# Automaton320.net
KiCad netlist of a schematic drawn in EAGLE
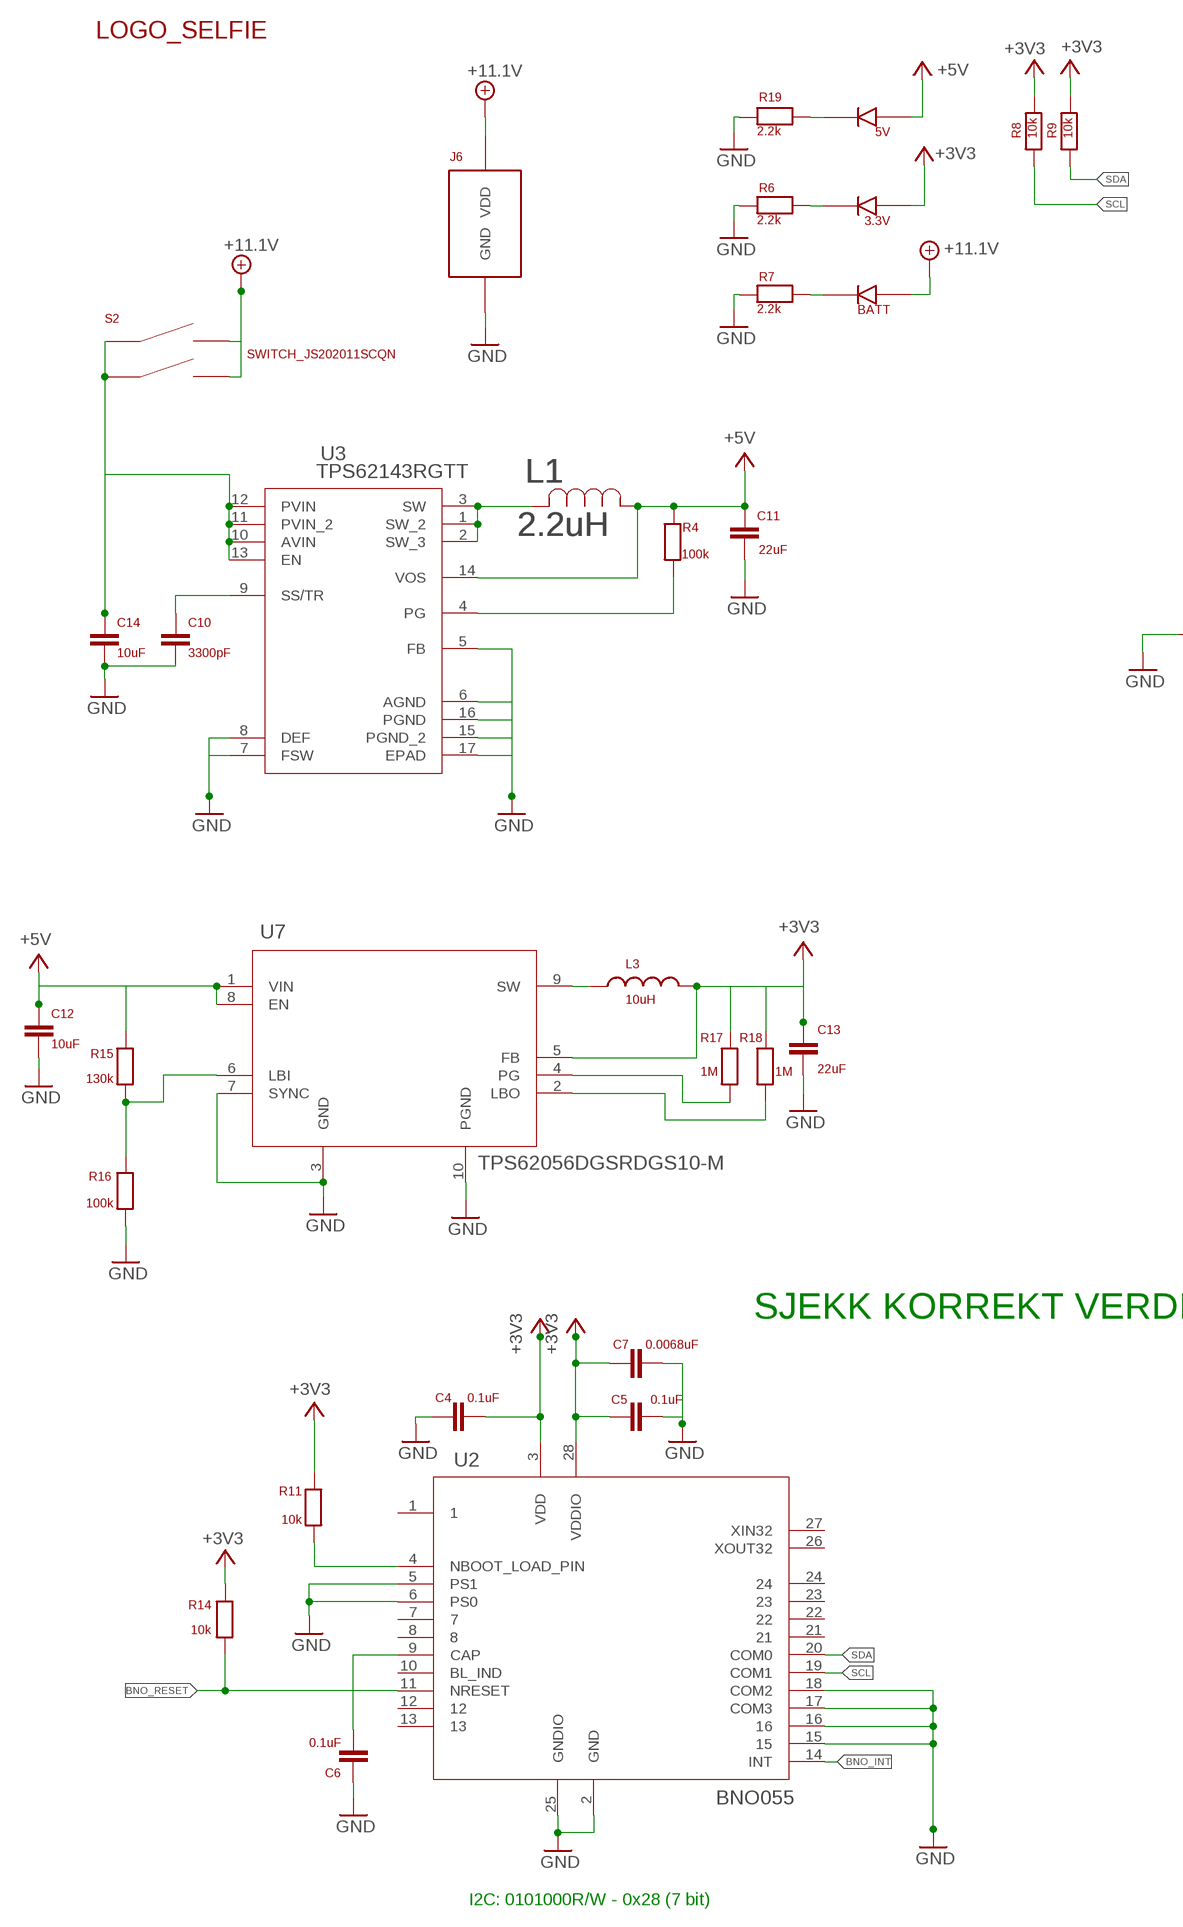
[diagram p0: schematic, sheet 1, part 1 of 2]
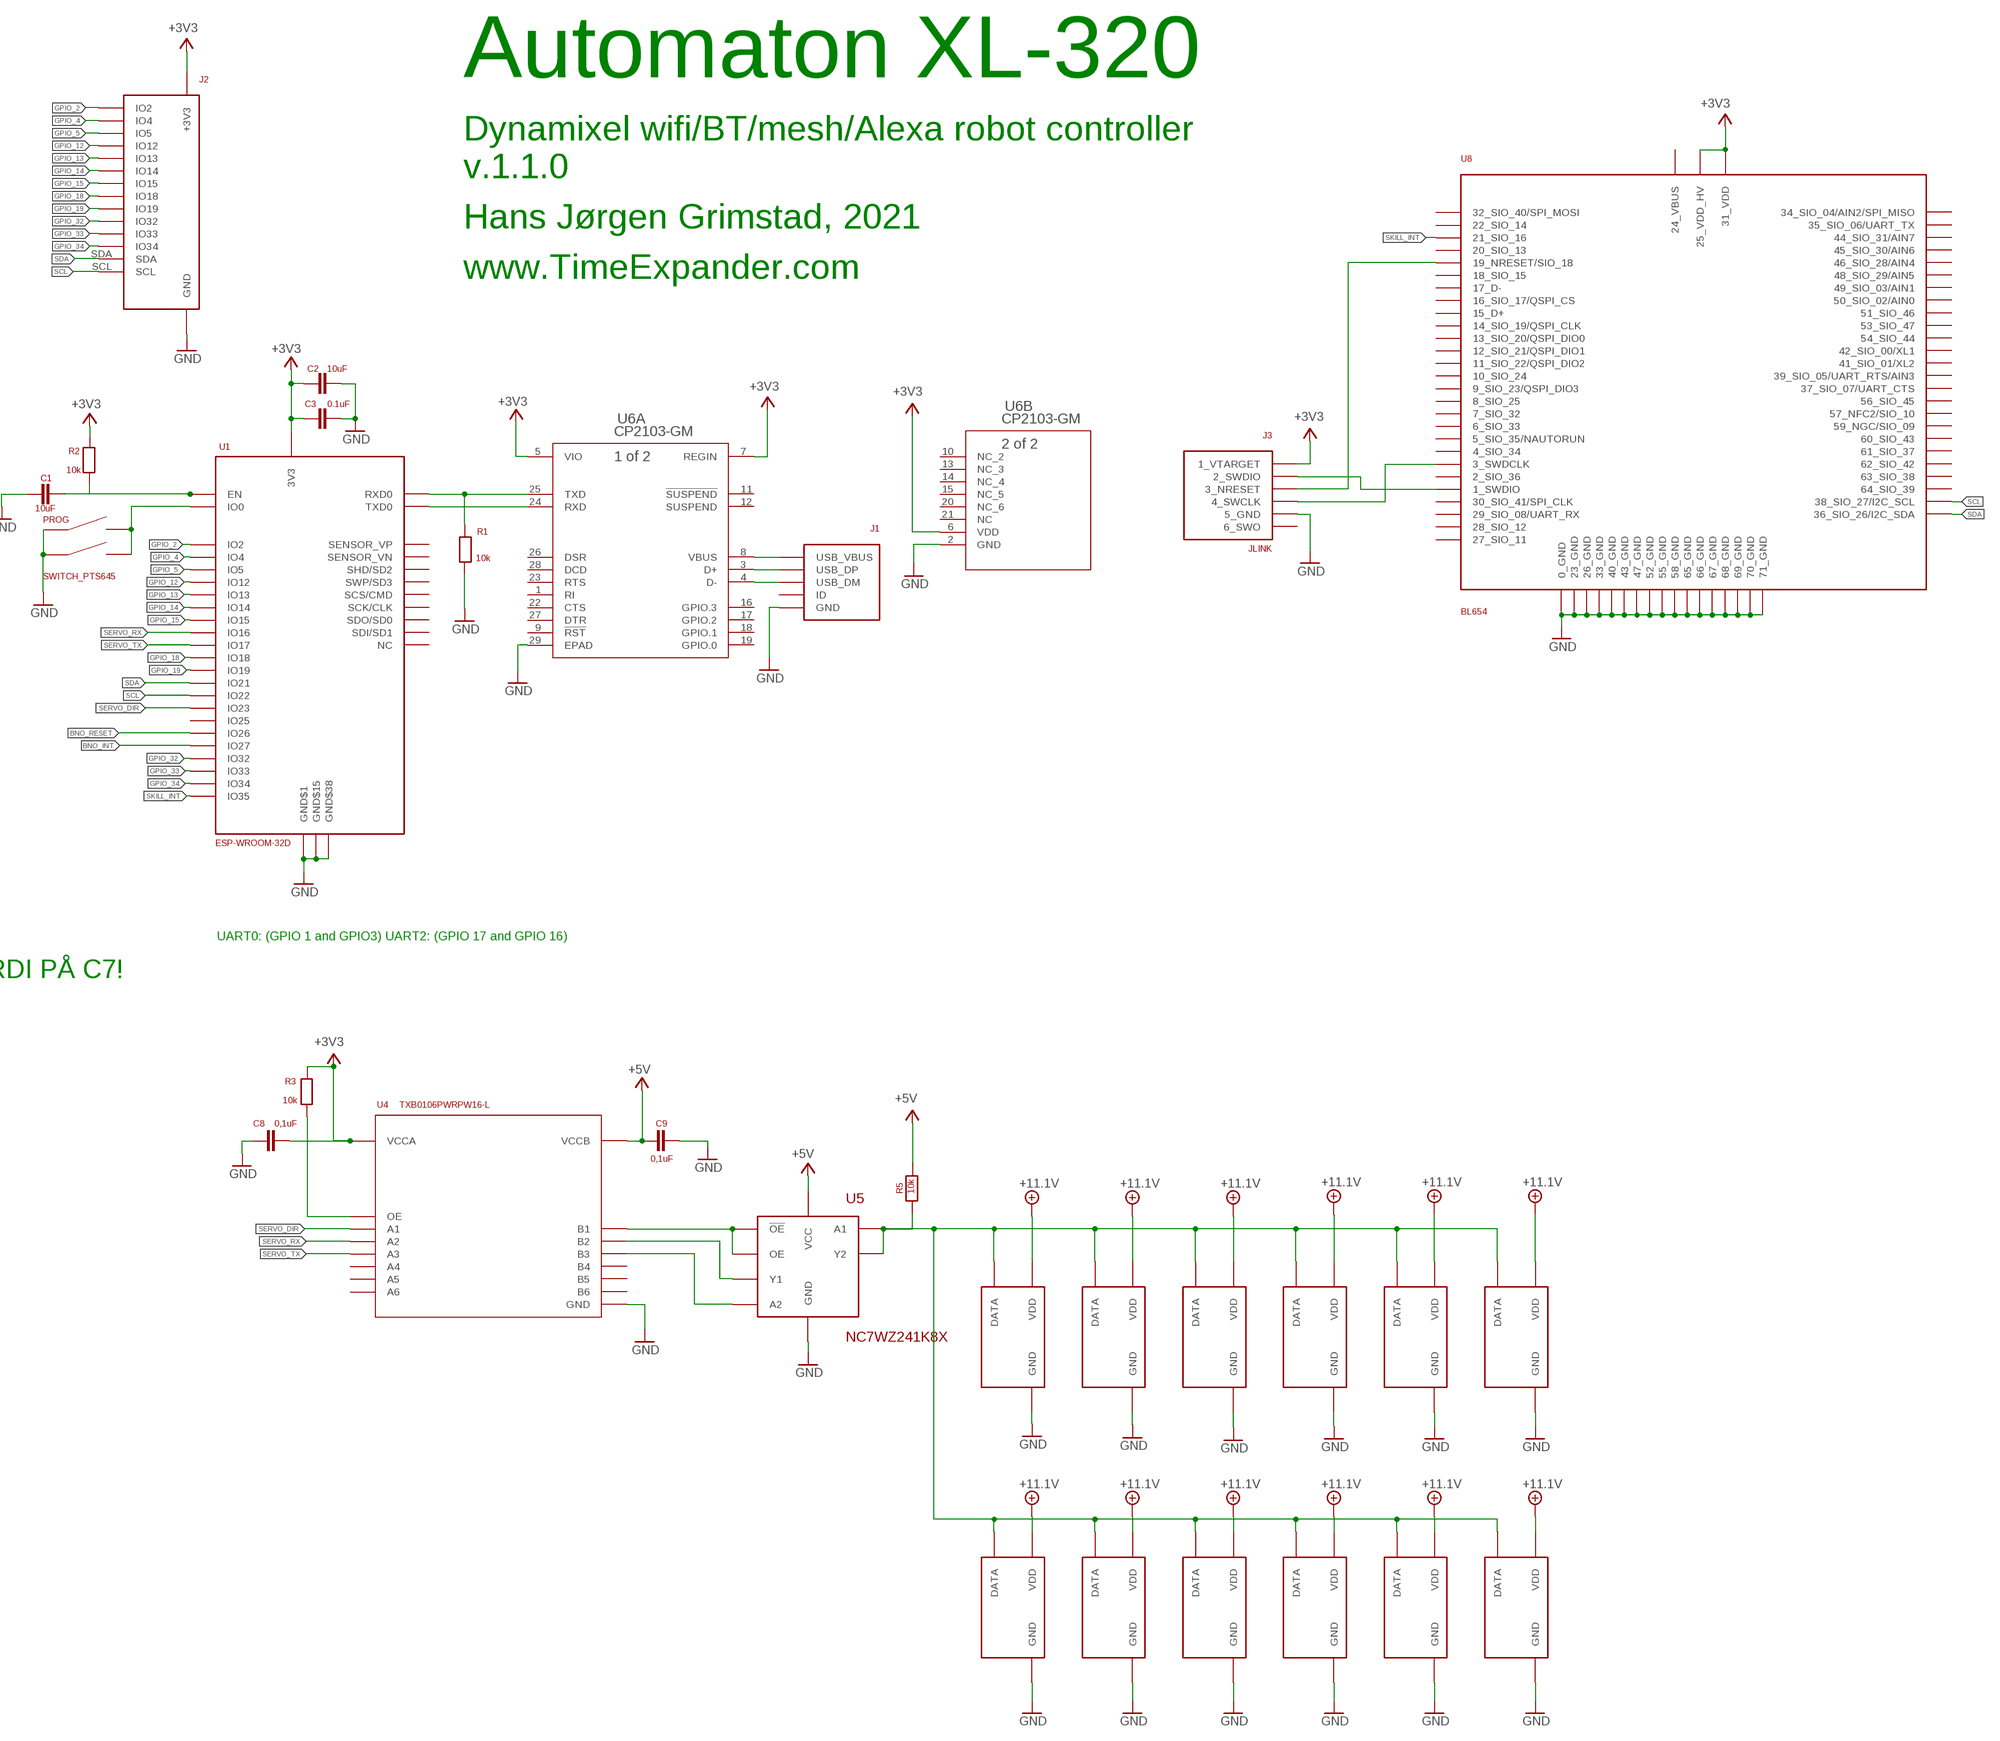
[diagram p1: schematic, sheet 1, part 2 of 2]

(export (version "E")
  (design (tool "Eeschema 10.0.6"))
  (components
    (comp (ref "3.3V")
      (value "LED_APTR3216PBC/A")
      (footprint "eagle-import:LED_APTR3216PBC_A")
      (libsource (lib "eagle-import") (part "LED_APTR3216PBC/A"))
    )
    (comp (ref "5V")
      (value "LED_APTR3216PBC/A")
      (footprint "eagle-import:LED_APTR3216PBC_A")
      (libsource (lib "eagle-import") (part "LED_APTR3216PBC/A"))
    )
    (comp (ref "BATT")
      (value "LED_APTR3216PBC/A")
      (footprint "eagle-import:LED_APTR3216PBC_A")
      (libsource (lib "eagle-import") (part "LED_APTR3216PBC/A"))
    )
    (comp (ref "C1")
      (value "10uF")
      (footprint "eagle-import:CAP_0402")
      (libsource (lib "eagle-import") (part "CAPACITOR0402"))
    )
    (comp (ref "C2")
      (value "10uF")
      (footprint "eagle-import:CAP_0402")
      (libsource (lib "eagle-import") (part "CAPACITOR0402"))
    )
    (comp (ref "C3")
      (value "0.1uF")
      (footprint "eagle-import:CAP_0402")
      (libsource (lib "eagle-import") (part "CAPACITOR0402"))
    )
    (comp (ref "C4")
      (value "0.1uF")
      (footprint "eagle-import:CAP_0402")
      (libsource (lib "eagle-import") (part "CAPACITOR0402"))
    )
    (comp (ref "C5")
      (value "0.1uF")
      (footprint "eagle-import:CAP_0402")
      (libsource (lib "eagle-import") (part "CAPACITOR0402"))
    )
    (comp (ref "C6")
      (value "0.1uF")
      (footprint "eagle-import:CAP_0402")
      (libsource (lib "eagle-import") (part "CAPACITOR0402"))
    )
    (comp (ref "C7")
      (value "0.0068uF")
      (footprint "eagle-import:CAP_0402")
      (libsource (lib "eagle-import") (part "CAPACITOR0402"))
    )
    (comp (ref "C8")
      (value "0,1uF")
      (footprint "eagle-import:CAP_0402")
      (libsource (lib "eagle-import") (part "CAPACITOR0402"))
    )
    (comp (ref "C9")
      (value "0,1uF")
      (footprint "eagle-import:CAP_0402")
      (libsource (lib "eagle-import") (part "CAPACITOR0402"))
    )
    (comp (ref "C10")
      (value "3300pF")
      (footprint "eagle-import:CAP_0402")
      (libsource (lib "eagle-import") (part "CAPACITOR0402"))
    )
    (comp (ref "C11")
      (value "22uF")
      (footprint "eagle-import:CAP_1206")
      (libsource (lib "eagle-import") (part "CAPACITOR1206"))
    )
    (comp (ref "C12")
      (value "10uF")
      (footprint "eagle-import:CAP_1206")
      (libsource (lib "eagle-import") (part "CAPACITOR1206"))
    )
    (comp (ref "C13")
      (value "22uF")
      (footprint "eagle-import:CAP_1206")
      (libsource (lib "eagle-import") (part "CAPACITOR1206"))
    )
    (comp (ref "C14")
      (value "10uF")
      (footprint "eagle-import:CAP_1206")
      (libsource (lib "eagle-import") (part "CAPACITOR1206"))
    )
    (comp (ref "DM1")
      (value "DYNAMIXEL_MOLEX_MINISPOX_3P_HEADERAX-12")
      (footprint "eagle-import:DYNAMIXEL_MOLEX_MINISPOX_3P_HEADER")
      (libsource (lib "eagle-import") (part "DYNAMIXEL_MOLEX_MINISPOX_3P_HEADERAX-12"))
    )
    (comp (ref "DM2")
      (value "DYNAMIXEL_MOLEX_MINISPOX_3P_HEADERAX-12")
      (footprint "eagle-import:DYNAMIXEL_MOLEX_MINISPOX_3P_HEADER")
      (libsource (lib "eagle-import") (part "DYNAMIXEL_MOLEX_MINISPOX_3P_HEADERAX-12"))
    )
    (comp (ref "DM3")
      (value "DYNAMIXEL_MOLEX_MINISPOX_3P_HEADERAX-12")
      (footprint "eagle-import:DYNAMIXEL_MOLEX_MINISPOX_3P_HEADER")
      (libsource (lib "eagle-import") (part "DYNAMIXEL_MOLEX_MINISPOX_3P_HEADERAX-12"))
    )
    (comp (ref "DM4")
      (value "DYNAMIXEL_MOLEX_MINISPOX_3P_HEADERAX-12")
      (footprint "eagle-import:DYNAMIXEL_MOLEX_MINISPOX_3P_HEADER")
      (libsource (lib "eagle-import") (part "DYNAMIXEL_MOLEX_MINISPOX_3P_HEADERAX-12"))
    )
    (comp (ref "DM5")
      (value "DYNAMIXEL_MOLEX_MINISPOX_3P_HEADERAX-12")
      (footprint "eagle-import:DYNAMIXEL_MOLEX_MINISPOX_3P_HEADER")
      (libsource (lib "eagle-import") (part "DYNAMIXEL_MOLEX_MINISPOX_3P_HEADERAX-12"))
    )
    (comp (ref "DM6")
      (value "DYNAMIXEL_MOLEX_MINISPOX_3P_HEADERAX-12")
      (footprint "eagle-import:DYNAMIXEL_MOLEX_MINISPOX_3P_HEADER")
      (libsource (lib "eagle-import") (part "DYNAMIXEL_MOLEX_MINISPOX_3P_HEADERAX-12"))
    )
    (comp (ref "J1")
      (value "USB_RCPT_10118192-0001LF")
      (footprint "eagle-import:USB_RCPT_10118192-0001LF")
      (libsource (lib "eagle-import") (part "USB_RCPT_10118192-0001LF"))
    )
    (comp (ref "J2")
      (value "ESP_ROBOT_BOARD_GPIO_16")
      (footprint "eagle-import:ESP_ROBOT_BOARD_GPIO_16")
      (libsource (lib "eagle-import") (part "ESP_ROBOT_BOARD_GPIO_16"))
    )
    (comp (ref "J3")
      (value "JLINK-6PIN")
      (footprint "eagle-import:JLINK-6PIN")
      (libsource (lib "eagle-import") (part "JLINK-6PIN"))
    )
    (comp (ref "J6")
      (value "BATTERY")
      (footprint "eagle-import:BATTERY_SOLDER_TERMINAL")
      (libsource (lib "eagle-import") (part "POWER_SOLDER_TERMINAL9V"))
    )
    (comp (ref "L1")
      (value "2.2uH")
      (footprint "eagle-import:IND_IHLP-1616AB-M")
      (fields (field (name "MANUFACTURER_PART_NUMBER") "IHLP1616ABER2R2M11"))
      (libsource (lib "eagle-import") (part "IHLP1616ABER2R2M11IND_IHLP-1616AB-M"))
    )
    (comp (ref "L3")
      (value "10uH")
      (footprint "eagle-import:IND_4028")
      (libsource (lib "eagle-import") (part "INDUCTOR_VLCF4024T-100MR90-2"))
    )
    (comp (ref "PROG")
      (value "SWITCH_PTS645")
      (footprint "eagle-import:SWITCH_PTS645_EE_NBIOT_01")
      (libsource (lib "eagle-import") (part "SWITCH_PTS645"))
    )
    (comp (ref "R1")
      (value "10k")
      (footprint "eagle-import:RES_0402")
      (libsource (lib "eagle-import") (part "TimeExpander2_21801758_RESISTOR"))
    )
    (comp (ref "R2")
      (value "10k")
      (footprint "eagle-import:RES_0402")
      (libsource (lib "eagle-import") (part "TimeExpander2_21801758_RESISTOR"))
    )
    (comp (ref "R3")
      (value "10k")
      (footprint "eagle-import:RES_0402")
      (libsource (lib "eagle-import") (part "TimeExpander2_21801758_RESISTOR"))
    )
    (comp (ref "R4")
      (value "100k")
      (footprint "eagle-import:RES_0402")
      (libsource (lib "eagle-import") (part "TimeExpander2_21801758_RESISTOR"))
    )
    (comp (ref "R5")
      (value "10k")
      (footprint "eagle-import:RES_0402")
      (libsource (lib "eagle-import") (part "TimeExpander2_21801758_RESISTOR"))
    )
    (comp (ref "R6")
      (value "2.2k")
      (footprint "eagle-import:RES_0402")
      (libsource (lib "eagle-import") (part "RESISTOR"))
    )
    (comp (ref "R7")
      (value "2.2k")
      (footprint "eagle-import:RES_0402")
      (libsource (lib "eagle-import") (part "RESISTOR"))
    )
    (comp (ref "R8")
      (value "10k")
      (footprint "eagle-import:RES_0402")
      (libsource (lib "eagle-import") (part "TimeExpander2_21801758_RESISTOR"))
    )
    (comp (ref "R9")
      (value "10k")
      (footprint "eagle-import:RES_0402")
      (libsource (lib "eagle-import") (part "TimeExpander2_21801758_RESISTOR"))
    )
    (comp (ref "R11")
      (value "10k")
      (footprint "eagle-import:RES_0402")
      (libsource (lib "eagle-import") (part "TimeExpander2_21801758_RESISTOR"))
    )
    (comp (ref "R14")
      (value "10k")
      (footprint "eagle-import:RES_0402")
      (libsource (lib "eagle-import") (part "TimeExpander2_21801758_RESISTOR"))
    )
    (comp (ref "R15")
      (value "130k")
      (footprint "eagle-import:RES_0402")
      (libsource (lib "eagle-import") (part "TimeExpander2_21801758_RESISTOR"))
    )
    (comp (ref "R16")
      (value "100k")
      (footprint "eagle-import:RES_0402")
      (libsource (lib "eagle-import") (part "TimeExpander2_21801758_RESISTOR"))
    )
    (comp (ref "R17")
      (value "1M")
      (footprint "eagle-import:RES_0402")
      (libsource (lib "eagle-import") (part "TimeExpander2_21801758_RESISTOR"))
    )
    (comp (ref "R18")
      (value "1M")
      (footprint "eagle-import:RES_0402")
      (libsource (lib "eagle-import") (part "TimeExpander2_21801758_RESISTOR"))
    )
    (comp (ref "R19")
      (value "2.2k")
      (footprint "eagle-import:RES_0402")
      (libsource (lib "eagle-import") (part "RESISTOR"))
    )
    (comp (ref "S2")
      (value "SWITCH_JS202011SCQN")
      (footprint "eagle-import:SWITCH_JS202011SCQN")
      (libsource (lib "eagle-import") (part "SWITCH_JS202011SCQN"))
    )
    (comp (ref "U$1")
      (value "DYNAMIXEL_MOLEX_MINISPOX_3P_HEADERXL-320")
      (footprint "eagle-import:DYNAMIXEL_MICROLATCH_3P_HEADER")
      (libsource (lib "eagle-import") (part "DYNAMIXEL_MOLEX_MINISPOX_3P_HEADERXL-320"))
    )
    (comp (ref "U$2")
      (value "LOGO_SELFIESELFIE_2")
      (footprint "eagle-import:TIMEEXPANDER_LOGO_1")
      (libsource (lib "eagle-import") (part "LOGO_SELFIESELFIE_2"))
    )
    (comp (ref "U$4")
      (value "DYNAMIXEL_MOLEX_MINISPOX_3P_HEADERXL-320")
      (footprint "eagle-import:DYNAMIXEL_MICROLATCH_3P_HEADER")
      (libsource (lib "eagle-import") (part "DYNAMIXEL_MOLEX_MINISPOX_3P_HEADERXL-320"))
    )
    (comp (ref "U$5")
      (value "DYNAMIXEL_MOLEX_MINISPOX_3P_HEADERXL-320")
      (footprint "eagle-import:DYNAMIXEL_MICROLATCH_3P_HEADER")
      (libsource (lib "eagle-import") (part "DYNAMIXEL_MOLEX_MINISPOX_3P_HEADERXL-320"))
    )
    (comp (ref "U$6")
      (value "DYNAMIXEL_MOLEX_MINISPOX_3P_HEADERXL-320")
      (footprint "eagle-import:DYNAMIXEL_MICROLATCH_3P_HEADER")
      (libsource (lib "eagle-import") (part "DYNAMIXEL_MOLEX_MINISPOX_3P_HEADERXL-320"))
    )
    (comp (ref "U$8")
      (value "DYNAMIXEL_MOLEX_MINISPOX_3P_HEADERXL-320")
      (footprint "eagle-import:DYNAMIXEL_MICROLATCH_3P_HEADER")
      (libsource (lib "eagle-import") (part "DYNAMIXEL_MOLEX_MINISPOX_3P_HEADERXL-320"))
    )
    (comp (ref "U$9")
      (value "DYNAMIXEL_MOLEX_MINISPOX_3P_HEADERXL-320")
      (footprint "eagle-import:DYNAMIXEL_MICROLATCH_3P_HEADER")
      (libsource (lib "eagle-import") (part "DYNAMIXEL_MOLEX_MINISPOX_3P_HEADERXL-320"))
    )
    (comp (ref "U1")
      (value "ESP-WROOM-32D")
      (footprint "eagle-import:ESP_WROOM_32D")
      (libsource (lib "eagle-import") (part "ESP-WROOM-32D"))
    )
    (comp (ref "U2")
      (value "BNO055")
      (footprint "eagle-import:QFN_BNO055")
      (fields (field (name "COPYRIGHT") "Copyright (C) 2018 Accelerated Designs. All rights reserved"))
      (libsource (lib "eagle-import") (part "BNO055"))
    )
    (comp (ref "U3")
      (value "TPS62143RGTT")
      (footprint "eagle-import:RGT16_1P7X1P7")
      (fields (field (name "MANUFACTURER") "Texas Instruments"))
      (libsource (lib "eagle-import") (part "TPS62143RGTT"))
    )
    (comp (ref "U4")
      (value "TXB0106PWRPW16-L")
      (footprint "eagle-import:PW16-L")
      (fields (field (name "MANUFACTURER_PART_NUMBER") "TXB0106PWR"))
      (libsource (lib "eagle-import") (part "TXB0106PWRPW16-L"))
    )
    (comp (ref "U5")
      (value "NC7WZ241K8X")
      (footprint "eagle-import:NC7WZ241K8X")
      (libsource (lib "eagle-import") (part "NC7WZ241K8X"))
    )
    (comp (ref "U6")
      (value "CP2103-GM")
      (footprint "eagle-import:QFN28_5X5_SIL-M")
      (libsource (lib "eagle-import") (part "CP2103-GMQFN28_5X5_SIL-M"))
    )
    (comp (ref "U7")
      (value "TPS62056DGSRDGS10-M")
      (footprint "eagle-import:DGS10-M")
      (fields
        (field (name "MANUFACTURER") "Texas Instruments")
        (field (name "MANUFACTURER_PART_NUMBER") "TPS62056DGSR")
      )
      (libsource (lib "eagle-import") (part "TPS62056DGSRDGS10-M"))
    )
    (comp (ref "U8")
      (value "BL654")
      (footprint "eagle-import:BL654")
      (libsource (lib "eagle-import") (part "BL654"))
    )
  )
  (nets
    (net (code "1") (name "+3V3") (class "Default")
      (node (ref "3.3V") (pin "A") (pinfunction "A_A") (pintype "passive"))
      (node (ref "C13") (pin "P$1") (pinfunction "1_P$1") (pintype "passive"))
      (node (ref "C2") (pin "P$1") (pinfunction "1_P$1") (pintype "passive"))
      (node (ref "C3") (pin "P$1") (pinfunction "1_P$1") (pintype "passive"))
      (node (ref "C4") (pin "P$2") (pinfunction "2_P$2") (pintype "passive"))
      (node (ref "C5") (pin "P$1") (pinfunction "1_P$1") (pintype "passive"))
      (node (ref "C7") (pin "P$1") (pinfunction "1_P$1") (pintype "passive"))
      (node (ref "C8") (pin "P$2") (pinfunction "2_P$2") (pintype "passive"))
      (node (ref "J2") (pin "+3V3") (pinfunction "+3V3_+3V3") (pintype "bidirectional"))
      (node (ref "J3") (pin "1_VTARGET") (pinfunction "1_VTARGET_1_VTARGET") (pintype "bidirectional"))
      (node (ref "L3") (pin "2") (pinfunction "2_2") (pintype "passive"))
      (node (ref "R11") (pin "P$2") (pinfunction "P$2_P$2") (pintype "bidirectional"))
      (node (ref "R14") (pin "P$2") (pinfunction "P$2_P$2") (pintype "bidirectional"))
      (node (ref "R17") (pin "P$2") (pinfunction "P$2_P$2") (pintype "bidirectional"))
      (node (ref "R18") (pin "P$2") (pinfunction "P$2_P$2") (pintype "bidirectional"))
      (node (ref "R2") (pin "P$2") (pinfunction "P$2_P$2") (pintype "bidirectional"))
      (node (ref "R3") (pin "P$2") (pinfunction "P$2_P$2") (pintype "bidirectional"))
      (node (ref "R8") (pin "P$2") (pinfunction "P$2_P$2") (pintype "bidirectional"))
      (node (ref "R9") (pin "P$2") (pinfunction "P$2_P$2") (pintype "bidirectional"))
      (node (ref "U1") (pin "2") (pinfunction "3V3_2") (pintype "bidirectional"))
      (node (ref "U2") (pin "28") (pinfunction "VDDIO_28") (pintype "power_in"))
      (node (ref "U2") (pin "3") (pinfunction "VDD_3") (pintype "power_in"))
      (node (ref "U4") (pin "2") (pinfunction "VCCA_2") (pintype "power_in"))
      (node (ref "U6") (pin "5") (pinfunction "VIO_5") (pintype "bidirectional"))
      (node (ref "U6") (pin "6") (pinfunction "VDD_6") (pintype "power_in"))
      (node (ref "U6") (pin "7") (pinfunction "REGIN_7") (pintype "input"))
      (node (ref "U7") (pin "5") (pinfunction "FB_5") (pintype "input"))
      (node (ref "U8") (pin "25") (pinfunction "25_VDD_HV_25") (pintype "bidirectional"))
      (node (ref "U8") (pin "31") (pinfunction "31_VDD_31") (pintype "bidirectional"))
    )
    (net (code "2") (name "+5V") (class "Default")
      (node (ref "5V") (pin "A") (pinfunction "A_A") (pintype "passive"))
      (node (ref "C11") (pin "P$1") (pinfunction "1_P$1") (pintype "passive"))
      (node (ref "C12") (pin "P$1") (pinfunction "1_P$1") (pintype "passive"))
      (node (ref "C9") (pin "P$1") (pinfunction "1_P$1") (pintype "passive"))
      (node (ref "L1") (pin "1") (pinfunction "1_1") (pintype "passive"))
      (node (ref "R15") (pin "P$2") (pinfunction "P$2_P$2") (pintype "bidirectional"))
      (node (ref "R4") (pin "P$2") (pinfunction "P$2_P$2") (pintype "bidirectional"))
      (node (ref "R5") (pin "P$2") (pinfunction "P$2_P$2") (pintype "bidirectional"))
      (node (ref "U3") (pin "14") (pinfunction "VOS_14") (pintype "input"))
      (node (ref "U4") (pin "15") (pinfunction "VCCB_15") (pintype "power_in"))
      (node (ref "U5") (pin "VCC") (pinfunction "VCC_VCC") (pintype "power_in"))
      (node (ref "U7") (pin "1") (pinfunction "VIN_1") (pintype "input"))
      (node (ref "U7") (pin "8") (pinfunction "EN_8") (pintype "input"))
    )
    (net (code "3") (name "+11.1V") (class "Default")
      (node (ref "BATT") (pin "A") (pinfunction "A_A") (pintype "passive"))
      (node (ref "DM1") (pin "VDD") (pinfunction "VDD_VDD") (pintype "bidirectional"))
      (node (ref "DM2") (pin "VDD") (pinfunction "VDD_VDD") (pintype "bidirectional"))
      (node (ref "DM3") (pin "VDD") (pinfunction "VDD_VDD") (pintype "bidirectional"))
      (node (ref "DM4") (pin "VDD") (pinfunction "VDD_VDD") (pintype "bidirectional"))
      (node (ref "DM5") (pin "VDD") (pinfunction "VDD_VDD") (pintype "bidirectional"))
      (node (ref "DM6") (pin "VDD") (pinfunction "VDD_VDD") (pintype "bidirectional"))
      (node (ref "J6") (pin "+") (pinfunction "VDD_+") (pintype "bidirectional"))
      (node (ref "S2") (pin "3") (pinfunction "B2_3") (pintype "bidirectional"))
      (node (ref "S2") (pin "6") (pinfunction "B1_6") (pintype "bidirectional"))
      (node (ref "U$1") (pin "VDD") (pinfunction "VDD_VDD") (pintype "bidirectional"))
      (node (ref "U$4") (pin "VDD") (pinfunction "VDD_VDD") (pintype "bidirectional"))
      (node (ref "U$5") (pin "VDD") (pinfunction "VDD_VDD") (pintype "bidirectional"))
      (node (ref "U$6") (pin "VDD") (pinfunction "VDD_VDD") (pintype "bidirectional"))
      (node (ref "U$8") (pin "VDD") (pinfunction "VDD_VDD") (pintype "bidirectional"))
      (node (ref "U$9") (pin "VDD") (pinfunction "VDD_VDD") (pintype "bidirectional"))
    )
    (net (code "4") (name "BNO_INT") (class "Default")
      (node (ref "U1") (pin "12") (pinfunction "IO27_12") (pintype "bidirectional"))
      (node (ref "U2") (pin "14") (pinfunction "INT_14") (pintype "passive"))
    )
    (net (code "5") (name "BNO_RESET") (class "Default")
      (node (ref "R14") (pin "P$1") (pinfunction "P$1_P$1") (pintype "bidirectional"))
      (node (ref "U1") (pin "11") (pinfunction "IO26_11") (pintype "bidirectional"))
      (node (ref "U2") (pin "11") (pinfunction "NRESET_11") (pintype "passive"))
    )
    (net (code "6") (name "GND") (class "Default")
      (node (ref "C1") (pin "P$1") (pinfunction "1_P$1") (pintype "passive"))
      (node (ref "C10") (pin "P$2") (pinfunction "2_P$2") (pintype "passive"))
      (node (ref "C11") (pin "P$2") (pinfunction "2_P$2") (pintype "passive"))
      (node (ref "C12") (pin "P$2") (pinfunction "2_P$2") (pintype "passive"))
      (node (ref "C13") (pin "P$2") (pinfunction "2_P$2") (pintype "passive"))
      (node (ref "C14") (pin "P$2") (pinfunction "2_P$2") (pintype "passive"))
      (node (ref "C2") (pin "P$2") (pinfunction "2_P$2") (pintype "passive"))
      (node (ref "C3") (pin "P$2") (pinfunction "2_P$2") (pintype "passive"))
      (node (ref "C4") (pin "P$1") (pinfunction "1_P$1") (pintype "passive"))
      (node (ref "C5") (pin "P$2") (pinfunction "2_P$2") (pintype "passive"))
      (node (ref "C6") (pin "P$1") (pinfunction "1_P$1") (pintype "passive"))
      (node (ref "C7") (pin "P$2") (pinfunction "2_P$2") (pintype "passive"))
      (node (ref "C8") (pin "P$1") (pinfunction "1_P$1") (pintype "passive"))
      (node (ref "C9") (pin "P$2") (pinfunction "2_P$2") (pintype "passive"))
      (node (ref "DM1") (pin "GND") (pinfunction "GND_GND") (pintype "bidirectional"))
      (node (ref "DM2") (pin "GND") (pinfunction "GND_GND") (pintype "bidirectional"))
      (node (ref "DM3") (pin "GND") (pinfunction "GND_GND") (pintype "bidirectional"))
      (node (ref "DM4") (pin "GND") (pinfunction "GND_GND") (pintype "bidirectional"))
      (node (ref "DM5") (pin "GND") (pinfunction "GND_GND") (pintype "bidirectional"))
      (node (ref "DM6") (pin "GND") (pinfunction "GND_GND") (pintype "bidirectional"))
      (node (ref "J1") (pin "GND") (pinfunction "GND_GND") (pintype "passive"))
      (node (ref "J2") (pin "GND") (pinfunction "GND_GND") (pintype "bidirectional"))
      (node (ref "J3") (pin "5_GND") (pinfunction "5_GND_5_GND") (pintype "bidirectional"))
      (node (ref "J6") (pin "-") (pinfunction "GND_-") (pintype "bidirectional"))
      (node (ref "PROG") (pin "A1") (pinfunction "A1_A1") (pintype "bidirectional"))
      (node (ref "PROG") (pin "A2") (pinfunction "A2_A2") (pintype "bidirectional"))
      (node (ref "R1") (pin "P$2") (pinfunction "P$2_P$2") (pintype "bidirectional"))
      (node (ref "R16") (pin "P$1") (pinfunction "P$1_P$1") (pintype "bidirectional"))
      (node (ref "R19") (pin "P$1") (pinfunction "P$1_P$1") (pintype "bidirectional"))
      (node (ref "R6") (pin "P$1") (pinfunction "P$1_P$1") (pintype "bidirectional"))
      (node (ref "R7") (pin "P$1") (pinfunction "P$1_P$1") (pintype "bidirectional"))
      (node (ref "U$1") (pin "GND") (pinfunction "GND_GND") (pintype "bidirectional"))
      (node (ref "U$4") (pin "GND") (pinfunction "GND_GND") (pintype "bidirectional"))
      (node (ref "U$5") (pin "GND") (pinfunction "GND_GND") (pintype "bidirectional"))
      (node (ref "U$6") (pin "GND") (pinfunction "GND_GND") (pintype "bidirectional"))
      (node (ref "U$8") (pin "GND") (pinfunction "GND_GND") (pintype "bidirectional"))
      (node (ref "U$9") (pin "GND") (pinfunction "GND_GND") (pintype "bidirectional"))
      (node (ref "U1") (pin "1") (pinfunction "GND$1_1") (pintype "bidirectional"))
      (node (ref "U1") (pin "15") (pinfunction "GND$15_15") (pintype "bidirectional"))
      (node (ref "U1") (pin "38") (pinfunction "GND$38_38") (pintype "bidirectional"))
      (node (ref "U1") (pin "GND$39") (pinfunction "GND$38_GND$39") (pintype "bidirectional"))
      (node (ref "U1") (pin "GND$40") (pinfunction "GND$38_GND$40") (pintype "bidirectional"))
      (node (ref "U1") (pin "GND$41") (pinfunction "GND$38_GND$41") (pintype "bidirectional"))
      (node (ref "U1") (pin "GND$42") (pinfunction "GND$38_GND$42") (pintype "bidirectional"))
      (node (ref "U1") (pin "GND$43") (pinfunction "GND$38_GND$43") (pintype "bidirectional"))
      (node (ref "U1") (pin "GND$44") (pinfunction "GND$38_GND$44") (pintype "bidirectional"))
      (node (ref "U1") (pin "GND$45") (pinfunction "GND$38_GND$45") (pintype "bidirectional"))
      (node (ref "U1") (pin "GND$46") (pinfunction "GND$38_GND$46") (pintype "bidirectional"))
      (node (ref "U1") (pin "GND$47") (pinfunction "GND$38_GND$47") (pintype "bidirectional"))
      (node (ref "U2") (pin "15") (pinfunction "15_15") (pintype "passive"))
      (node (ref "U2") (pin "16") (pinfunction "16_16") (pintype "passive"))
      (node (ref "U2") (pin "17") (pinfunction "COM3_17") (pintype "bidirectional"))
      (node (ref "U2") (pin "18") (pinfunction "COM2_18") (pintype "bidirectional"))
      (node (ref "U2") (pin "2") (pinfunction "GND_2") (pintype "passive"))
      (node (ref "U2") (pin "25") (pinfunction "GNDIO_25") (pintype "passive"))
      (node (ref "U2") (pin "5") (pinfunction "PS1_5") (pintype "bidirectional"))
      (node (ref "U2") (pin "6") (pinfunction "PS0_6") (pintype "bidirectional"))
      (node (ref "U3") (pin "15") (pinfunction "PGND_2_15") (pintype "power_in"))
      (node (ref "U3") (pin "16") (pinfunction "PGND_16") (pintype "power_in"))
      (node (ref "U3") (pin "17") (pinfunction "EPAD_17") (pintype "passive"))
      (node (ref "U3") (pin "5") (pinfunction "FB_5") (pintype "input"))
      (node (ref "U3") (pin "6") (pinfunction "AGND_6") (pintype "power_in"))
      (node (ref "U3") (pin "7") (pinfunction "FSW_7") (pintype "input"))
      (node (ref "U3") (pin "8") (pinfunction "DEF_8") (pintype "input"))
      (node (ref "U4") (pin "9") (pinfunction "GND_9") (pintype "power_in"))
      (node (ref "U5") (pin "GND") (pinfunction "GND_GND") (pintype "power_in"))
      (node (ref "U6") (pin "2") (pinfunction "GND_2") (pintype "power_in"))
      (node (ref "U6") (pin "29") (pinfunction "EPAD_29") (pintype "passive"))
      (node (ref "U7") (pin "10") (pinfunction "PGND_10") (pintype "input"))
      (node (ref "U7") (pin "3") (pinfunction "GND_3") (pintype "input"))
      (node (ref "U7") (pin "7") (pinfunction "SYNC_7") (pintype "input"))
      (node (ref "U8") (pin "0") (pinfunction "0_GND_0") (pintype "bidirectional"))
      (node (ref "U8") (pin "23") (pinfunction "23_GND_23") (pintype "bidirectional"))
      (node (ref "U8") (pin "26") (pinfunction "26_GND_26") (pintype "bidirectional"))
      (node (ref "U8") (pin "33") (pinfunction "33_GND_33") (pintype "bidirectional"))
      (node (ref "U8") (pin "40") (pinfunction "40_GND_40") (pintype "bidirectional"))
      (node (ref "U8") (pin "43") (pinfunction "43_GND_43") (pintype "bidirectional"))
      (node (ref "U8") (pin "47") (pinfunction "47_GND_47") (pintype "bidirectional"))
      (node (ref "U8") (pin "52") (pinfunction "52_GND_52") (pintype "bidirectional"))
      (node (ref "U8") (pin "55") (pinfunction "55_GND_55") (pintype "bidirectional"))
      (node (ref "U8") (pin "58") (pinfunction "58_GND_58") (pintype "bidirectional"))
      (node (ref "U8") (pin "65") (pinfunction "65_GND_65") (pintype "bidirectional"))
      (node (ref "U8") (pin "66") (pinfunction "66_GND_66") (pintype "bidirectional"))
      (node (ref "U8") (pin "67") (pinfunction "67_GND_67") (pintype "bidirectional"))
      (node (ref "U8") (pin "68") (pinfunction "68_GND_68") (pintype "bidirectional"))
      (node (ref "U8") (pin "69") (pinfunction "69_GND_69") (pintype "bidirectional"))
      (node (ref "U8") (pin "70") (pinfunction "70_GND_70") (pintype "bidirectional"))
      (node (ref "U8") (pin "71") (pinfunction "71_GND_71") (pintype "bidirectional"))
    )
    (net (code "7") (name "GPIO_2") (class "Default")
      (node (ref "J2") (pin "IO2") (pinfunction "IO2_IO2") (pintype "bidirectional"))
      (node (ref "U1") (pin "24") (pinfunction "IO2_24") (pintype "bidirectional"))
    )
    (net (code "8") (name "GPIO_4") (class "Default")
      (node (ref "J2") (pin "IO4") (pinfunction "IO4_IO4") (pintype "bidirectional"))
      (node (ref "U1") (pin "26") (pinfunction "IO4_26") (pintype "bidirectional"))
    )
    (net (code "9") (name "GPIO_5") (class "Default")
      (node (ref "J2") (pin "IO5") (pinfunction "IO5_IO5") (pintype "bidirectional"))
      (node (ref "U1") (pin "29") (pinfunction "IO5_29") (pintype "bidirectional"))
    )
    (net (code "10") (name "GPIO_12") (class "Default")
      (node (ref "J2") (pin "IO12") (pinfunction "IO12_IO12") (pintype "bidirectional"))
      (node (ref "U1") (pin "14") (pinfunction "IO12_14") (pintype "bidirectional"))
    )
    (net (code "11") (name "GPIO_13") (class "Default")
      (node (ref "J2") (pin "IO13") (pinfunction "IO13_IO13") (pintype "bidirectional"))
      (node (ref "U1") (pin "16") (pinfunction "IO13_16") (pintype "bidirectional"))
    )
    (net (code "12") (name "GPIO_14") (class "Default")
      (node (ref "J2") (pin "IO14") (pinfunction "IO14_IO14") (pintype "bidirectional"))
      (node (ref "U1") (pin "13") (pinfunction "IO14_13") (pintype "bidirectional"))
    )
    (net (code "13") (name "GPIO_15") (class "Default")
      (node (ref "J2") (pin "IO15") (pinfunction "IO15_IO15") (pintype "bidirectional"))
      (node (ref "U1") (pin "23") (pinfunction "IO15_23") (pintype "bidirectional"))
    )
    (net (code "14") (name "GPIO_18") (class "Default")
      (node (ref "J2") (pin "IO18") (pinfunction "IO18_IO18") (pintype "bidirectional"))
      (node (ref "U1") (pin "30") (pinfunction "IO18_30") (pintype "bidirectional"))
    )
    (net (code "15") (name "GPIO_19") (class "Default")
      (node (ref "J2") (pin "IO19") (pinfunction "IO19_IO19") (pintype "bidirectional"))
      (node (ref "U1") (pin "31") (pinfunction "IO19_31") (pintype "bidirectional"))
    )
    (net (code "16") (name "GPIO_32") (class "Default")
      (node (ref "J2") (pin "IO32") (pinfunction "IO32_IO32") (pintype "bidirectional"))
      (node (ref "U1") (pin "8") (pinfunction "IO32_8") (pintype "bidirectional"))
    )
    (net (code "17") (name "GPIO_33") (class "Default")
      (node (ref "J2") (pin "IO33") (pinfunction "IO33_IO33") (pintype "bidirectional"))
      (node (ref "U1") (pin "9") (pinfunction "IO33_9") (pintype "bidirectional"))
    )
    (net (code "18") (name "GPIO_34") (class "Default")
      (node (ref "J2") (pin "IO34") (pinfunction "IO34_IO34") (pintype "bidirectional"))
      (node (ref "U1") (pin "6") (pinfunction "IO34_6") (pintype "bidirectional"))
    )
    (net (code "19") (name "Net-(3.3V-PadC)") (class "Default")
      (node (ref "3.3V") (pin "C") (pinfunction "C_C") (pintype "passive"))
      (node (ref "R6") (pin "P$2") (pinfunction "P$2_P$2") (pintype "bidirectional"))
    )
    (net (code "20") (name "Net-(5V-PadC)") (class "Default")
      (node (ref "5V") (pin "C") (pinfunction "C_C") (pintype "passive"))
      (node (ref "R19") (pin "P$2") (pinfunction "P$2_P$2") (pintype "bidirectional"))
    )
    (net (code "21") (name "Net-(BATT-PadC)") (class "Default")
      (node (ref "BATT") (pin "C") (pinfunction "C_C") (pintype "passive"))
      (node (ref "R7") (pin "P$2") (pinfunction "P$2_P$2") (pintype "bidirectional"))
    )
    (net (code "22") (name "Net-(C1-2)") (class "Default")
      (node (ref "C1") (pin "P$2") (pinfunction "2_P$2") (pintype "passive"))
      (node (ref "R2") (pin "P$1") (pinfunction "P$1_P$1") (pintype "bidirectional"))
      (node (ref "U1") (pin "3") (pinfunction "EN_3") (pintype "bidirectional"))
    )
    (net (code "23") (name "Net-(C6-2)") (class "Default")
      (node (ref "C6") (pin "P$2") (pinfunction "2_P$2") (pintype "passive"))
      (node (ref "U2") (pin "9") (pinfunction "CAP_9") (pintype "passive"))
    )
    (net (code "24") (name "Net-(C10-1)") (class "Default")
      (node (ref "C10") (pin "P$1") (pinfunction "1_P$1") (pintype "passive"))
      (node (ref "U3") (pin "9") (pinfunction "SS/TR_9") (pintype "input"))
    )
    (net (code "25") (name "Net-(C14-1)") (class "Default")
      (node (ref "C14") (pin "P$1") (pinfunction "1_P$1") (pintype "passive"))
      (node (ref "S2") (pin "2") (pinfunction "A2_2") (pintype "bidirectional"))
      (node (ref "S2") (pin "5") (pinfunction "A1_5") (pintype "bidirectional"))
      (node (ref "U3") (pin "10") (pinfunction "AVIN_10") (pintype "input"))
      (node (ref "U3") (pin "11") (pinfunction "PVIN_2_11") (pintype "input"))
      (node (ref "U3") (pin "12") (pinfunction "PVIN_12") (pintype "input"))
      (node (ref "U3") (pin "13") (pinfunction "EN_13") (pintype "input"))
    )
    (net (code "26") (name "Net-(DM1-PadDATA)") (class "Default")
      (node (ref "DM1") (pin "DATA") (pinfunction "DATA_DATA") (pintype "bidirectional"))
      (node (ref "DM2") (pin "DATA") (pinfunction "DATA_DATA") (pintype "bidirectional"))
      (node (ref "DM3") (pin "DATA") (pinfunction "DATA_DATA") (pintype "bidirectional"))
      (node (ref "DM4") (pin "DATA") (pinfunction "DATA_DATA") (pintype "bidirectional"))
      (node (ref "DM5") (pin "DATA") (pinfunction "DATA_DATA") (pintype "bidirectional"))
      (node (ref "DM6") (pin "DATA") (pinfunction "DATA_DATA") (pintype "bidirectional"))
      (node (ref "R5") (pin "P$1") (pinfunction "P$1_P$1") (pintype "bidirectional"))
      (node (ref "U$1") (pin "DATA") (pinfunction "DATA_DATA") (pintype "bidirectional"))
      (node (ref "U$4") (pin "DATA") (pinfunction "DATA_DATA") (pintype "bidirectional"))
      (node (ref "U$5") (pin "DATA") (pinfunction "DATA_DATA") (pintype "bidirectional"))
      (node (ref "U$6") (pin "DATA") (pinfunction "DATA_DATA") (pintype "bidirectional"))
      (node (ref "U$8") (pin "DATA") (pinfunction "DATA_DATA") (pintype "bidirectional"))
      (node (ref "U$9") (pin "DATA") (pinfunction "DATA_DATA") (pintype "bidirectional"))
      (node (ref "U5") (pin "A1") (pinfunction "A1_A1") (pintype "power_in"))
      (node (ref "U5") (pin "Y2") (pinfunction "Y2_Y2") (pintype "power_in"))
    )
    (net (code "27") (name "Net-(J1-USB_DM)") (class "Default")
      (node (ref "J1") (pin "D-") (pinfunction "USB_DM_D-") (pintype "passive"))
      (node (ref "U6") (pin "4") (pinfunction "D-_4") (pintype "bidirectional"))
    )
    (net (code "28") (name "Net-(J1-USB_DP)") (class "Default")
      (node (ref "J1") (pin "D+") (pinfunction "USB_DP_D+") (pintype "passive"))
      (node (ref "U6") (pin "3") (pinfunction "D+_3") (pintype "bidirectional"))
    )
    (net (code "29") (name "Net-(J1-USB_VBUS)") (class "Default")
      (node (ref "J1") (pin "VCC") (pinfunction "USB_VBUS_VCC") (pintype "passive"))
      (node (ref "U6") (pin "8") (pinfunction "VBUS_8") (pintype "input"))
    )
    (net (code "30") (name "Net-(J3-4_SWCLK)") (class "Default")
      (node (ref "J3") (pin "4_SWDCLK") (pinfunction "4_SWCLK_4_SWDCLK") (pintype "bidirectional"))
      (node (ref "U8") (pin "3") (pinfunction "3_SWDCLK_3") (pintype "bidirectional"))
    )
    (net (code "31") (name "Net-(U1-IO0)") (class "Default")
      (node (ref "PROG") (pin "B1") (pinfunction "B1_B1") (pintype "bidirectional"))
      (node (ref "PROG") (pin "B2") (pinfunction "B2_B2") (pintype "bidirectional"))
      (node (ref "U1") (pin "25") (pinfunction "IO0_25") (pintype "bidirectional"))
    )
    (net (code "32") (name "Net-(U1-RXD0)") (class "Default")
      (node (ref "R1") (pin "P$1") (pinfunction "P$1_P$1") (pintype "bidirectional"))
      (node (ref "U1") (pin "34") (pinfunction "RXD0_34") (pintype "bidirectional"))
      (node (ref "U6") (pin "25") (pinfunction "TXD_25") (pintype "output"))
    )
    (net (code "33") (name "Net-(U1-TXD0)") (class "Default")
      (node (ref "U1") (pin "35") (pinfunction "TXD0_35") (pintype "bidirectional"))
      (node (ref "U6") (pin "24") (pinfunction "RXD_24") (pintype "input"))
    )
    (net (code "34") (name "Net-(U2-NBOOT_LOAD_PIN)") (class "Default")
      (node (ref "R11") (pin "P$1") (pinfunction "P$1_P$1") (pintype "bidirectional"))
      (node (ref "U2") (pin "4") (pinfunction "NBOOT_LOAD_PIN_4") (pintype "passive"))
    )
    (net (code "35") (name "Net-(U3-PG)") (class "Default")
      (node (ref "R4") (pin "P$1") (pinfunction "P$1_P$1") (pintype "bidirectional"))
      (node (ref "U3") (pin "4") (pinfunction "PG_4") (pintype "output"))
    )
    (net (code "36") (name "Net-(U3-SW)") (class "Default")
      (node (ref "L1") (pin "2") (pinfunction "2_2") (pintype "passive"))
      (node (ref "U3") (pin "1") (pinfunction "SW_2_1") (pintype "output"))
      (node (ref "U3") (pin "2") (pinfunction "SW_3_2") (pintype "output"))
      (node (ref "U3") (pin "3") (pinfunction "SW_3") (pintype "output"))
    )
    (net (code "37") (name "Net-(U4-B1)") (class "Default")
      (node (ref "U4") (pin "16") (pinfunction "B1_16") (pintype "bidirectional"))
      (node (ref "U5") (pin "!OE") (pinfunction "~{OE}_!OE") (pintype "power_in"))
      (node (ref "U5") (pin "OE") (pinfunction "OE_OE") (pintype "power_in"))
    )
    (net (code "38") (name "Net-(U4-B2)") (class "Default")
      (node (ref "U4") (pin "14") (pinfunction "B2_14") (pintype "bidirectional"))
      (node (ref "U5") (pin "Y1") (pinfunction "Y1_Y1") (pintype "power_in"))
    )
    (net (code "39") (name "Net-(U4-B3)") (class "Default")
      (node (ref "U4") (pin "13") (pinfunction "B3_13") (pintype "bidirectional"))
      (node (ref "U5") (pin "A2") (pinfunction "A2_A2") (pintype "power_in"))
    )
    (net (code "40") (name "Net-(U4-OE)") (class "Default")
      (node (ref "R3") (pin "P$1") (pinfunction "P$1_P$1") (pintype "bidirectional"))
      (node (ref "U4") (pin "8") (pinfunction "OE_8") (pintype "output"))
    )
    (net (code "41") (name "Net-(U7-LBI)") (class "Default")
      (node (ref "R15") (pin "P$1") (pinfunction "P$1_P$1") (pintype "bidirectional"))
      (node (ref "R16") (pin "P$2") (pinfunction "P$2_P$2") (pintype "bidirectional"))
      (node (ref "U7") (pin "6") (pinfunction "LBI_6") (pintype "input"))
    )
    (net (code "42") (name "Net-(U7-LBO)") (class "Default")
      (node (ref "R18") (pin "P$1") (pinfunction "P$1_P$1") (pintype "bidirectional"))
      (node (ref "U7") (pin "2") (pinfunction "LBO_2") (pintype "output"))
    )
    (net (code "43") (name "Net-(U7-PG)") (class "Default")
      (node (ref "R17") (pin "P$1") (pinfunction "P$1_P$1") (pintype "bidirectional"))
      (node (ref "U7") (pin "4") (pinfunction "PG_4") (pintype "output"))
    )
    (net (code "44") (name "Net-(U7-SW)") (class "Default")
      (node (ref "L3") (pin "1") (pinfunction "1_1") (pintype "passive"))
      (node (ref "U7") (pin "9") (pinfunction "SW_9") (pintype "output"))
    )
    (net (code "45") (name "Net-(U8-1_SWDIO)") (class "Default")
      (node (ref "J3") (pin "2_SWDIO") (pinfunction "2_SWDIO_2_SWDIO") (pintype "bidirectional"))
      (node (ref "U8") (pin "1") (pinfunction "1_SWDIO_1") (pintype "bidirectional"))
    )
    (net (code "46") (name "Net-(U8-19_NRESET{slash}SIO_18)") (class "Default")
      (node (ref "J3") (pin "3_NRESET") (pinfunction "3_NRESET_3_NRESET") (pintype "bidirectional"))
      (node (ref "U8") (pin "19") (pinfunction "19_NRESET/SIO_18_19") (pintype "bidirectional"))
    )
    (net (code "47") (name "SCL") (class "Default")
      (node (ref "J2") (pin "SCL") (pinfunction "SCL_SCL") (pintype "bidirectional"))
      (node (ref "R8") (pin "P$1") (pinfunction "P$1_P$1") (pintype "bidirectional"))
      (node (ref "U1") (pin "36") (pinfunction "IO22_36") (pintype "bidirectional"))
      (node (ref "U2") (pin "19") (pinfunction "COM1_19") (pintype "bidirectional"))
      (node (ref "U8") (pin "38") (pinfunction "38_SIO_27/I2C_SCL_38") (pintype "bidirectional"))
    )
    (net (code "48") (name "SDA") (class "Default")
      (node (ref "J2") (pin "SDA") (pinfunction "SDA_SDA") (pintype "bidirectional"))
      (node (ref "R9") (pin "P$1") (pinfunction "P$1_P$1") (pintype "bidirectional"))
      (node (ref "U1") (pin "33") (pinfunction "IO21_33") (pintype "bidirectional"))
      (node (ref "U2") (pin "20") (pinfunction "COM0_20") (pintype "bidirectional"))
      (node (ref "U8") (pin "36") (pinfunction "36_SIO_26/I2C_SDA_36") (pintype "bidirectional"))
    )
    (net (code "49") (name "SERVO_DIR") (class "Default")
      (node (ref "U1") (pin "37") (pinfunction "IO23_37") (pintype "bidirectional"))
      (node (ref "U4") (pin "1") (pinfunction "A1_1") (pintype "bidirectional"))
    )
    (net (code "50") (name "SERVO_RX") (class "Default")
      (node (ref "U1") (pin "27") (pinfunction "IO16_27") (pintype "bidirectional"))
      (node (ref "U4") (pin "3") (pinfunction "A2_3") (pintype "bidirectional"))
    )
    (net (code "51") (name "SERVO_TX") (class "Default")
      (node (ref "U1") (pin "28") (pinfunction "IO17_28") (pintype "bidirectional"))
      (node (ref "U4") (pin "4") (pinfunction "A3_4") (pintype "bidirectional"))
    )
    (net (code "52") (name "SKILL_INT") (class "Default")
      (node (ref "U1") (pin "7") (pinfunction "IO35_7") (pintype "bidirectional"))
      (node (ref "U8") (pin "21") (pinfunction "21_SIO_16_21") (pintype "bidirectional"))
    )
    (net (code "53") (name "unconnected-(J1-PadID)") (class "Default")
      (node (ref "J1") (pin "ID") (pinfunction "ID_ID") (pintype "passive"))
    )
    (net (code "54") (name "unconnected-(J3-Pad6_SWO)") (class "Default")
      (node (ref "J3") (pin "6_SWO") (pinfunction "6_SWO_6_SWO") (pintype "bidirectional"))
    )
    (net (code "55") (name "unconnected-(U1-IO25-Pad10)") (class "Default")
      (node (ref "U1") (pin "10") (pinfunction "IO25_10") (pintype "bidirectional"))
    )
    (net (code "56") (name "unconnected-(U1-NC-Pad32)") (class "Default")
      (node (ref "U1") (pin "32") (pinfunction "NC_32") (pintype "bidirectional"))
    )
    (net (code "57") (name "unconnected-(U1-SCK{slash}CLK-Pad20)") (class "Default")
      (node (ref "U1") (pin "20") (pinfunction "SCK/CLK_20") (pintype "bidirectional"))
    )
    (net (code "58") (name "unconnected-(U1-SCS{slash}CMD-Pad19)") (class "Default")
      (node (ref "U1") (pin "19") (pinfunction "SCS/CMD_19") (pintype "bidirectional"))
    )
    (net (code "59") (name "unconnected-(U1-SDI{slash}SD1-Pad22)") (class "Default")
      (node (ref "U1") (pin "22") (pinfunction "SDI/SD1_22") (pintype "bidirectional"))
    )
    (net (code "60") (name "unconnected-(U1-SDO{slash}SD0-Pad21)") (class "Default")
      (node (ref "U1") (pin "21") (pinfunction "SDO/SD0_21") (pintype "bidirectional"))
    )
    (net (code "61") (name "unconnected-(U1-SENSOR_VN-Pad5)") (class "Default")
      (node (ref "U1") (pin "5") (pinfunction "SENSOR_VN_5") (pintype "bidirectional"))
    )
    (net (code "62") (name "unconnected-(U1-SENSOR_VP-Pad4)") (class "Default")
      (node (ref "U1") (pin "4") (pinfunction "SENSOR_VP_4") (pintype "bidirectional"))
    )
    (net (code "63") (name "unconnected-(U1-SHD{slash}SD2-Pad17)") (class "Default")
      (node (ref "U1") (pin "17") (pinfunction "SHD/SD2_17") (pintype "bidirectional"))
    )
    (net (code "64") (name "unconnected-(U1-SWP{slash}SD3-Pad18)") (class "Default")
      (node (ref "U1") (pin "18") (pinfunction "SWP/SD3_18") (pintype "bidirectional"))
    )
    (net (code "65") (name "unconnected-(U2-BL_IND-Pad10)") (class "Default")
      (node (ref "U2") (pin "10") (pinfunction "BL_IND_10") (pintype "passive"))
    )
    (net (code "66") (name "unconnected-(U2-Pad1)") (class "Default")
      (node (ref "U2") (pin "1") (pinfunction "1_1") (pintype "passive"))
    )
    (net (code "67") (name "unconnected-(U2-Pad7)") (class "Default")
      (node (ref "U2") (pin "7") (pinfunction "7_7") (pintype "passive"))
    )
    (net (code "68") (name "unconnected-(U2-Pad8)") (class "Default")
      (node (ref "U2") (pin "8") (pinfunction "8_8") (pintype "passive"))
    )
    (net (code "69") (name "unconnected-(U2-Pad12)") (class "Default")
      (node (ref "U2") (pin "12") (pinfunction "12_12") (pintype "passive"))
    )
    (net (code "70") (name "unconnected-(U2-Pad13)") (class "Default")
      (node (ref "U2") (pin "13") (pinfunction "13_13") (pintype "passive"))
    )
    (net (code "71") (name "unconnected-(U2-Pad21)") (class "Default")
      (node (ref "U2") (pin "21") (pinfunction "21_21") (pintype "passive"))
    )
    (net (code "72") (name "unconnected-(U2-Pad22)") (class "Default")
      (node (ref "U2") (pin "22") (pinfunction "22_22") (pintype "passive"))
    )
    (net (code "73") (name "unconnected-(U2-Pad23)") (class "Default")
      (node (ref "U2") (pin "23") (pinfunction "23_23") (pintype "passive"))
    )
    (net (code "74") (name "unconnected-(U2-Pad24)") (class "Default")
      (node (ref "U2") (pin "24") (pinfunction "24_24") (pintype "passive"))
    )
    (net (code "75") (name "unconnected-(U2-XIN32-Pad27)") (class "Default")
      (node (ref "U2") (pin "27") (pinfunction "XIN32_27") (pintype "input"))
    )
    (net (code "76") (name "unconnected-(U2-XOUT32-Pad26)") (class "Default")
      (node (ref "U2") (pin "26") (pinfunction "XOUT32_26") (pintype "output"))
    )
    (net (code "77") (name "unconnected-(U4-A4-Pad5)") (class "Default")
      (node (ref "U4") (pin "5") (pinfunction "A4_5") (pintype "bidirectional"))
    )
    (net (code "78") (name "unconnected-(U4-A5-Pad6)") (class "Default")
      (node (ref "U4") (pin "6") (pinfunction "A5_6") (pintype "bidirectional"))
    )
    (net (code "79") (name "unconnected-(U4-A6-Pad7)") (class "Default")
      (node (ref "U4") (pin "7") (pinfunction "A6_7") (pintype "bidirectional"))
    )
    (net (code "80") (name "unconnected-(U4-B4-Pad12)") (class "Default")
      (node (ref "U4") (pin "12") (pinfunction "B4_12") (pintype "bidirectional"))
    )
    (net (code "81") (name "unconnected-(U4-B5-Pad11)") (class "Default")
      (node (ref "U4") (pin "11") (pinfunction "B5_11") (pintype "bidirectional"))
    )
    (net (code "82") (name "unconnected-(U4-B6-Pad10)") (class "Default")
      (node (ref "U4") (pin "10") (pinfunction "B6_10") (pintype "bidirectional"))
    )
    (net (code "83") (name "unconnected-(U6A-CTS-Pad22)") (class "Default")
      (node (ref "U6") (pin "22") (pinfunction "CTS_22") (pintype "input"))
    )
    (net (code "84") (name "unconnected-(U6A-DCD-Pad28)") (class "Default")
      (node (ref "U6") (pin "28") (pinfunction "DCD_28") (pintype "input"))
    )
    (net (code "85") (name "unconnected-(U6A-DSR-Pad26)") (class "Default")
      (node (ref "U6") (pin "26") (pinfunction "DSR_26") (pintype "input"))
    )
    (net (code "86") (name "unconnected-(U6A-DTR-Pad27)") (class "Default")
      (node (ref "U6") (pin "27") (pinfunction "DTR_27") (pintype "output"))
    )
    (net (code "87") (name "unconnected-(U6A-GPIO.0-Pad19)") (class "Default")
      (node (ref "U6") (pin "19") (pinfunction "GPIO.0_19") (pintype "bidirectional"))
    )
    (net (code "88") (name "unconnected-(U6A-GPIO.1-Pad18)") (class "Default")
      (node (ref "U6") (pin "18") (pinfunction "GPIO.1_18") (pintype "bidirectional"))
    )
    (net (code "89") (name "unconnected-(U6A-GPIO.2-Pad17)") (class "Default")
      (node (ref "U6") (pin "17") (pinfunction "GPIO.2_17") (pintype "bidirectional"))
    )
    (net (code "90") (name "unconnected-(U6A-GPIO.3-Pad16)") (class "Default")
      (node (ref "U6") (pin "16") (pinfunction "GPIO.3_16") (pintype "bidirectional"))
    )
    (net (code "91") (name "unconnected-(U6A-RI-Pad1)") (class "Default")
      (node (ref "U6") (pin "1") (pinfunction "RI_1") (pintype "input"))
    )
    (net (code "92") (name "unconnected-(U6A-RTS-Pad23)") (class "Default")
      (node (ref "U6") (pin "23") (pinfunction "RTS_23") (pintype "output"))
    )
    (net (code "93") (name "unconnected-(U6A-SUSPEND-Pad12)") (class "Default")
      (node (ref "U6") (pin "12") (pinfunction "SUSPEND_12") (pintype "output"))
    )
    (net (code "94") (name "unconnected-(U6A-~{RST}-Pad9)") (class "Default")
      (node (ref "U6") (pin "9") (pinfunction "~{RST}_9") (pintype "bidirectional"))
    )
    (net (code "95") (name "unconnected-(U6A-~{SUSPEND}-Pad11)") (class "Default")
      (node (ref "U6") (pin "11") (pinfunction "~{SUSPEND}_11") (pintype "output"))
    )
    (net (code "96") (name "unconnected-(U6B-NC-Pad21)") (class "Default")
      (node (ref "U6") (pin "21") (pinfunction "NC_21") (pintype "no_connect"))
    )
    (net (code "97") (name "unconnected-(U6B-NC_2-Pad10)") (class "Default")
      (node (ref "U6") (pin "10") (pinfunction "NC_2_10") (pintype "no_connect"))
    )
    (net (code "98") (name "unconnected-(U6B-NC_3-Pad13)") (class "Default")
      (node (ref "U6") (pin "13") (pinfunction "NC_3_13") (pintype "no_connect"))
    )
    (net (code "99") (name "unconnected-(U6B-NC_4-Pad14)") (class "Default")
      (node (ref "U6") (pin "14") (pinfunction "NC_4_14") (pintype "no_connect"))
    )
    (net (code "100") (name "unconnected-(U6B-NC_5-Pad15)") (class "Default")
      (node (ref "U6") (pin "15") (pinfunction "NC_5_15") (pintype "no_connect"))
    )
    (net (code "101") (name "unconnected-(U6B-NC_6-Pad20)") (class "Default")
      (node (ref "U6") (pin "20") (pinfunction "NC_6_20") (pintype "no_connect"))
    )
    (net (code "102") (name "unconnected-(U8-2_SIO_36-Pad2)") (class "Default")
      (node (ref "U8") (pin "2") (pinfunction "2_SIO_36_2") (pintype "bidirectional"))
    )
    (net (code "103") (name "unconnected-(U8-4_SIO_34-Pad4)") (class "Default")
      (node (ref "U8") (pin "4") (pinfunction "4_SIO_34_4") (pintype "bidirectional"))
    )
    (net (code "104") (name "unconnected-(U8-5_SIO_35{slash}NAUTORUN-Pad5)") (class "Default")
      (node (ref "U8") (pin "5") (pinfunction "5_SIO_35/NAUTORUN_5") (pintype "bidirectional"))
    )
    (net (code "105") (name "unconnected-(U8-6_SIO_33-Pad6)") (class "Default")
      (node (ref "U8") (pin "6") (pinfunction "6_SIO_33_6") (pintype "bidirectional"))
    )
    (net (code "106") (name "unconnected-(U8-7_SIO_32-Pad7)") (class "Default")
      (node (ref "U8") (pin "7") (pinfunction "7_SIO_32_7") (pintype "bidirectional"))
    )
    (net (code "107") (name "unconnected-(U8-8_SIO_25-Pad8)") (class "Default")
      (node (ref "U8") (pin "8") (pinfunction "8_SIO_25_8") (pintype "bidirectional"))
    )
    (net (code "108") (name "unconnected-(U8-9_SIO_23{slash}QSPI_DIO3-Pad9)") (class "Default")
      (node (ref "U8") (pin "9") (pinfunction "9_SIO_23/QSPI_DIO3_9") (pintype "bidirectional"))
    )
    (net (code "109") (name "unconnected-(U8-10_SIO_24-Pad10)") (class "Default")
      (node (ref "U8") (pin "10") (pinfunction "10_SIO_24_10") (pintype "bidirectional"))
    )
    (net (code "110") (name "unconnected-(U8-11_SIO_22{slash}QSPI_DIO2-Pad11)") (class "Default")
      (node (ref "U8") (pin "11") (pinfunction "11_SIO_22/QSPI_DIO2_11") (pintype "bidirectional"))
    )
    (net (code "111") (name "unconnected-(U8-12_SIO_21{slash}QSPI_DIO1-Pad12)") (class "Default")
      (node (ref "U8") (pin "12") (pinfunction "12_SIO_21/QSPI_DIO1_12") (pintype "bidirectional"))
    )
    (net (code "112") (name "unconnected-(U8-13_SIO_20{slash}QSPI_DIO0-Pad13)") (class "Default")
      (node (ref "U8") (pin "13") (pinfunction "13_SIO_20/QSPI_DIO0_13") (pintype "bidirectional"))
    )
    (net (code "113") (name "unconnected-(U8-14_SIO_19{slash}QSPI_CLK-Pad14)") (class "Default")
      (node (ref "U8") (pin "14") (pinfunction "14_SIO_19/QSPI_CLK_14") (pintype "bidirectional"))
    )
    (net (code "114") (name "unconnected-(U8-15_D+-Pad15)") (class "Default")
      (node (ref "U8") (pin "15") (pinfunction "15_D+_15") (pintype "bidirectional"))
    )
    (net (code "115") (name "unconnected-(U8-16_SIO_17{slash}QSPI_CS-Pad16)") (class "Default")
      (node (ref "U8") (pin "16") (pinfunction "16_SIO_17/QSPI_CS_16") (pintype "bidirectional"))
    )
    (net (code "116") (name "unconnected-(U8-17_D--Pad17)") (class "Default")
      (node (ref "U8") (pin "17") (pinfunction "17_D-_17") (pintype "bidirectional"))
    )
    (net (code "117") (name "unconnected-(U8-18_SIO_15-Pad18)") (class "Default")
      (node (ref "U8") (pin "18") (pinfunction "18_SIO_15_18") (pintype "bidirectional"))
    )
    (net (code "118") (name "unconnected-(U8-20_SIO_13-Pad20)") (class "Default")
      (node (ref "U8") (pin "20") (pinfunction "20_SIO_13_20") (pintype "bidirectional"))
    )
    (net (code "119") (name "unconnected-(U8-22_SIO_14-Pad22)") (class "Default")
      (node (ref "U8") (pin "22") (pinfunction "22_SIO_14_22") (pintype "bidirectional"))
    )
    (net (code "120") (name "unconnected-(U8-24_VBUS-Pad24)") (class "Default")
      (node (ref "U8") (pin "24") (pinfunction "24_VBUS_24") (pintype "bidirectional"))
    )
    (net (code "121") (name "unconnected-(U8-27_SIO_11-Pad27)") (class "Default")
      (node (ref "U8") (pin "27") (pinfunction "27_SIO_11_27") (pintype "bidirectional"))
    )
    (net (code "122") (name "unconnected-(U8-28_SIO_12-Pad28)") (class "Default")
      (node (ref "U8") (pin "28") (pinfunction "28_SIO_12_28") (pintype "bidirectional"))
    )
    (net (code "123") (name "unconnected-(U8-29_SIO_08{slash}UART_RX-Pad29)") (class "Default")
      (node (ref "U8") (pin "29") (pinfunction "29_SIO_08/UART_RX_29") (pintype "bidirectional"))
    )
    (net (code "124") (name "unconnected-(U8-30_SIO_41{slash}SPI_CLK-Pad30)") (class "Default")
      (node (ref "U8") (pin "30") (pinfunction "30_SIO_41/SPI_CLK_30") (pintype "bidirectional"))
    )
    (net (code "125") (name "unconnected-(U8-32_SIO_40{slash}SPI_MOSI-Pad32)") (class "Default")
      (node (ref "U8") (pin "32") (pinfunction "32_SIO_40/SPI_MOSI_32") (pintype "bidirectional"))
    )
    (net (code "126") (name "unconnected-(U8-34_SIO_04{slash}AIN2{slash}SPI_MISO-Pad34)") (class "Default")
      (node (ref "U8") (pin "34") (pinfunction "34_SIO_04/AIN2/SPI_MISO_34") (pintype "bidirectional"))
    )
    (net (code "127") (name "unconnected-(U8-35_SIO_06{slash}UART_TX-Pad35)") (class "Default")
      (node (ref "U8") (pin "35") (pinfunction "35_SIO_06/UART_TX_35") (pintype "bidirectional"))
    )
    (net (code "128") (name "unconnected-(U8-37_SIO_07{slash}UART_CTS-Pad37)") (class "Default")
      (node (ref "U8") (pin "37") (pinfunction "37_SIO_07/UART_CTS_37") (pintype "bidirectional"))
    )
    (net (code "129") (name "unconnected-(U8-39_SIO_05{slash}UART_RTS{slash}AIN3-Pad39)") (class "Default")
      (node (ref "U8") (pin "39") (pinfunction "39_SIO_05/UART_RTS/AIN3_39") (pintype "bidirectional"))
    )
    (net (code "130") (name "unconnected-(U8-41_SIO_01{slash}XL2-Pad41)") (class "Default")
      (node (ref "U8") (pin "41") (pinfunction "41_SIO_01/XL2_41") (pintype "bidirectional"))
    )
    (net (code "131") (name "unconnected-(U8-42_SIO_00{slash}XL1-Pad42)") (class "Default")
      (node (ref "U8") (pin "42") (pinfunction "42_SIO_00/XL1_42") (pintype "bidirectional"))
    )
    (net (code "132") (name "unconnected-(U8-44_SIO_31{slash}AIN7-Pad44)") (class "Default")
      (node (ref "U8") (pin "44") (pinfunction "44_SIO_31/AIN7_44") (pintype "bidirectional"))
    )
    (net (code "133") (name "unconnected-(U8-45_SIO_30{slash}AIN6-Pad45)") (class "Default")
      (node (ref "U8") (pin "45") (pinfunction "45_SIO_30/AIN6_45") (pintype "bidirectional"))
    )
    (net (code "134") (name "unconnected-(U8-46_SIO_28{slash}AIN4-Pad46)") (class "Default")
      (node (ref "U8") (pin "46") (pinfunction "46_SIO_28/AIN4_46") (pintype "bidirectional"))
    )
    (net (code "135") (name "unconnected-(U8-48_SIO_29{slash}AIN5-Pad48)") (class "Default")
      (node (ref "U8") (pin "48") (pinfunction "48_SIO_29/AIN5_48") (pintype "bidirectional"))
    )
    (net (code "136") (name "unconnected-(U8-49_SIO_03{slash}AIN1-Pad49)") (class "Default")
      (node (ref "U8") (pin "49") (pinfunction "49_SIO_03/AIN1_49") (pintype "bidirectional"))
    )
    (net (code "137") (name "unconnected-(U8-50_SIO_02{slash}AIN0-Pad50)") (class "Default")
      (node (ref "U8") (pin "50") (pinfunction "50_SIO_02/AIN0_50") (pintype "bidirectional"))
    )
    (net (code "138") (name "unconnected-(U8-51_SIO_46-Pad51)") (class "Default")
      (node (ref "U8") (pin "51") (pinfunction "51_SIO_46_51") (pintype "bidirectional"))
    )
    (net (code "139") (name "unconnected-(U8-53_SIO_47-Pad53)") (class "Default")
      (node (ref "U8") (pin "53") (pinfunction "53_SIO_47_53") (pintype "bidirectional"))
    )
    (net (code "140") (name "unconnected-(U8-54_SIO_44-Pad54)") (class "Default")
      (node (ref "U8") (pin "54") (pinfunction "54_SIO_44_54") (pintype "bidirectional"))
    )
    (net (code "141") (name "unconnected-(U8-56_SIO_45-Pad56)") (class "Default")
      (node (ref "U8") (pin "56") (pinfunction "56_SIO_45_56") (pintype "bidirectional"))
    )
    (net (code "142") (name "unconnected-(U8-57_NFC2{slash}SIO_10-Pad57)") (class "Default")
      (node (ref "U8") (pin "57") (pinfunction "57_NFC2/SIO_10_57") (pintype "bidirectional"))
    )
    (net (code "143") (name "unconnected-(U8-59_NGC{slash}SIO_09-Pad59)") (class "Default")
      (node (ref "U8") (pin "59") (pinfunction "59_NGC/SIO_09_59") (pintype "bidirectional"))
    )
    (net (code "144") (name "unconnected-(U8-60_SIO_43-Pad60)") (class "Default")
      (node (ref "U8") (pin "60") (pinfunction "60_SIO_43_60") (pintype "bidirectional"))
    )
    (net (code "145") (name "unconnected-(U8-61_SIO_37-Pad61)") (class "Default")
      (node (ref "U8") (pin "61") (pinfunction "61_SIO_37_61") (pintype "bidirectional"))
    )
    (net (code "146") (name "unconnected-(U8-62_SIO_42-Pad62)") (class "Default")
      (node (ref "U8") (pin "62") (pinfunction "62_SIO_42_62") (pintype "bidirectional"))
    )
    (net (code "147") (name "unconnected-(U8-63_SIO_38-Pad63)") (class "Default")
      (node (ref "U8") (pin "63") (pinfunction "63_SIO_38_63") (pintype "bidirectional"))
    )
    (net (code "148") (name "unconnected-(U8-64_SIO_39-Pad64)") (class "Default")
      (node (ref "U8") (pin "64") (pinfunction "64_SIO_39_64") (pintype "bidirectional"))
    )
  )
)
